# PreCharge.net
KiCad netlist of a schematic drawn in Altium Designer
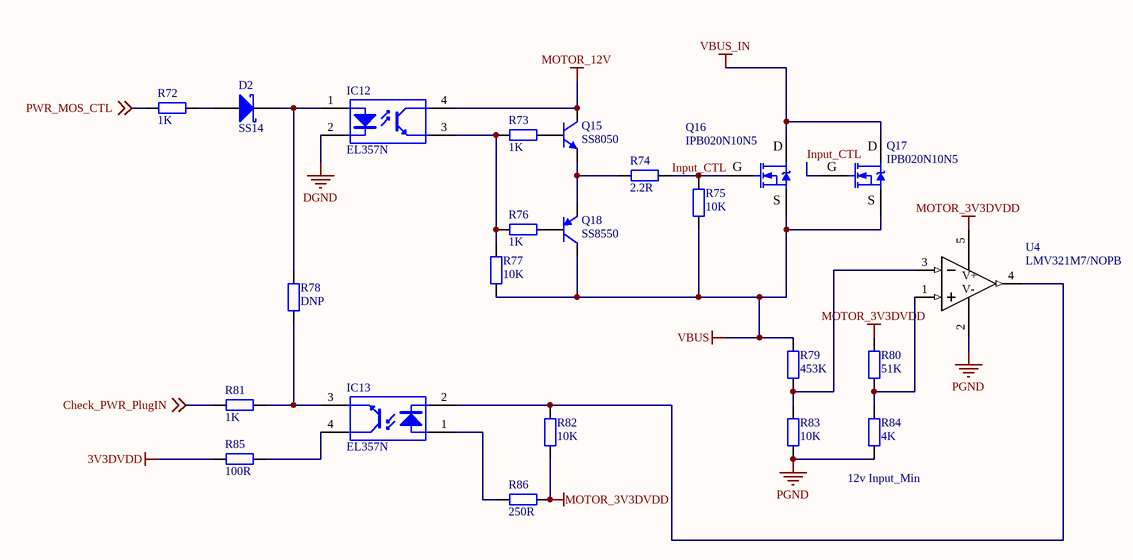
[diagram p0: PreCharge.SchDoc]

(export (version "E")
  (design (tool "Eeschema 10.0.6"))
  (components
    (comp (ref "D2")
      (value "SS14")
      (footprint "SMA")
      (description "肖特基二极管")
      (libsource (lib "0.2 -  二极管-整流桥") (part "SS14"))
    )
    (comp (ref "IC12")
      (value "EL357N")
      (footprint "DIP4-300")
      (description "线性光耦")
      (fields (field (name "版权归属") "封装库来自淘宝 ID：黄晶宝石"))
      (libsource (lib "1.2 - 传感元件") (part "EL357N"))
    )
    (comp (ref "IC13")
      (value "EL357N")
      (footprint "DIP4-300")
      (description "线性光耦")
      (fields (field (name "版权归属") "封装库来自淘宝 ID：黄晶宝石"))
      (libsource (lib "1.2 - 传感元件") (part "EL357N"))
    )
    (comp (ref "Q15")
      (value "SS8050")
      (footprint "SOT23-3N")
      (description "高频放大-NPN型")
      (fields (field (name "版权归属") "封装库来自淘宝 ID：黄晶宝石"))
      (libsource (lib "0.4 - 三极管") (part "8050-SMD"))
    )
    (comp (ref "Q16")
      (value "IPB020N10N5")
      (footprint "TO252")
      (description "N沟道场效应管")
      (libsource (lib "0.5 - 场效应管-可控硅") (part "SI2302"))
    )
    (comp (ref "Q17")
      (value "IPB020N10N5")
      (footprint "TO252")
      (description "N沟道场效应管")
      (libsource (lib "0.5 - 场效应管-可控硅") (part "SI2302"))
    )
    (comp (ref "Q18")
      (value "SS8550")
      (footprint "SOT23-3N")
      (description "高频放大-PNP型")
      (fields (field (name "版权归属") "封装库来自淘宝 ID：黄晶宝石"))
      (libsource (lib "0.4 - 三极管") (part "8550-SMD"))
    )
    (comp (ref "R72")
      (value "1K")
      (footprint "R 0603_L")
      (description "贴片电阻")
      (libsource (lib "0.1 - 电阻-电容-电感") (part "R"))
    )
    (comp (ref "R73")
      (value "1K")
      (footprint "R 0603_L")
      (description "贴片电阻")
      (libsource (lib "0.1 - 电阻-电容-电感") (part "R"))
    )
    (comp (ref "R74")
      (value "2.2R")
      (footprint "R 0603_L")
      (description "贴片电阻")
      (libsource (lib "0.1 - 电阻-电容-电感") (part "R"))
    )
    (comp (ref "R75")
      (value "10K")
      (footprint "R 0603_L")
      (description "贴片电阻")
      (libsource (lib "0.1 - 电阻-电容-电感") (part "R"))
    )
    (comp (ref "R76")
      (value "1K")
      (footprint "R 0603_L")
      (description "贴片电阻")
      (libsource (lib "0.1 - 电阻-电容-电感") (part "R"))
    )
    (comp (ref "R77")
      (value "10K")
      (footprint "R 0603_L")
      (description "贴片电阻")
      (libsource (lib "0.1 - 电阻-电容-电感") (part "R"))
    )
    (comp (ref "R78")
      (value "DNP")
      (footprint "R 0603_L")
      (description "贴片电阻")
      (libsource (lib "0.1 - 电阻-电容-电感") (part "R"))
    )
    (comp (ref "R79")
      (value "453K")
      (footprint "R 0603_L")
      (description "贴片电阻")
      (libsource (lib "0.1 - 电阻-电容-电感") (part "R"))
    )
    (comp (ref "R80")
      (value "51K")
      (footprint "R 0603_L")
      (description "贴片电阻")
      (libsource (lib "0.1 - 电阻-电容-电感") (part "R"))
    )
    (comp (ref "R81")
      (value "1K")
      (footprint "R 0603_L")
      (description "贴片电阻")
      (libsource (lib "0.1 - 电阻-电容-电感") (part "R"))
    )
    (comp (ref "R82")
      (value "10K")
      (footprint "R 0603_L")
      (description "贴片电阻")
      (libsource (lib "0.1 - 电阻-电容-电感") (part "R"))
    )
    (comp (ref "R83")
      (value "10K")
      (footprint "R 0603_L")
      (description "贴片电阻")
      (libsource (lib "0.1 - 电阻-电容-电感") (part "R"))
    )
    (comp (ref "R84")
      (value "4K")
      (footprint "R 0603_L")
      (description "贴片电阻")
      (libsource (lib "0.1 - 电阻-电容-电感") (part "R"))
    )
    (comp (ref "R85")
      (value "100R")
      (footprint "R 0603_L")
      (description "贴片电阻")
      (libsource (lib "0.1 - 电阻-电容-电感") (part "R"))
    )
    (comp (ref "R86")
      (value "250R")
      (footprint "R 0603_L")
      (description "贴片电阻")
      (libsource (lib "0.1 - 电阻-电容-电感") (part "R"))
    )
    (comp (ref "U4")
      (value "LMV321M7/NOPB")
      (footprint "MAA05A")
      (description "No Description Available")
      (fields
        (field (name "PARTNUMBER") "LMV321M7")
        (field (name "MANUFACTURER") "NationalSemiconductor")
        (field (name "COPYRIGHT") "Copyright (C) 2023 Ultra Librarian. All rights reserved.")
        (field (name "PUBLISHER") "NationalSemiconductor")
      )
      (libsource (lib "SkylakeADSchLib") (part "LMV321M7/NOPB"))
    )
  )
  (nets
    (net (code "1") (name "/Input_CTL") (class "Default")
      (node (ref "Q16") (pin "1") (pinfunction "G_1") (pintype "passive"))
      (node (ref "Q17") (pin "1") (pinfunction "G_1") (pintype "passive"))
      (node (ref "R74") (pin "1") (pinfunction "1_1") (pintype "passive"))
      (node (ref "R75") (pin "1") (pinfunction "1_1") (pintype "passive"))
    )
    (net (code "2") (name "3V3DVDD") (class "Default")
      (node (ref "R85") (pin "1") (pinfunction "1_1") (pintype "passive"))
    )
    (net (code "3") (name "Check_PWR_PlugIN") (class "Default")
      (node (ref "R81") (pin "2") (pinfunction "2_2") (pintype "passive"))
    )
    (net (code "4") (name "DGND") (class "Default")
      (node (ref "IC12") (pin "2") (pinfunction "K_2") (pintype "passive"))
    )
    (net (code "5") (name "MOTOR_3V3DVDD") (class "Default")
      (node (ref "R80") (pin "1") (pinfunction "1_1") (pintype "passive"))
      (node (ref "R82") (pin "2") (pinfunction "2_2") (pintype "passive"))
      (node (ref "R86") (pin "1") (pinfunction "1_1") (pintype "passive"))
      (node (ref "U4") (pin "5") (pinfunction "V+_5") (pintype "power_in"))
    )
    (net (code "6") (name "MOTOR_12V") (class "Default")
      (node (ref "IC12") (pin "4") (pinfunction "C_4") (pintype "passive"))
      (node (ref "Q15") (pin "3") (pinfunction "C_3") (pintype "passive"))
    )
    (net (code "7") (name "Net-(D2-A)") (class "Default")
      (node (ref "D2") (pin "1") (pinfunction "A_1") (pintype "passive"))
      (node (ref "R72") (pin "1") (pinfunction "1_1") (pintype "passive"))
    )
    (net (code "8") (name "Net-(D2-K)") (class "Default")
      (node (ref "D2") (pin "2") (pinfunction "K_2") (pintype "passive"))
      (node (ref "IC12") (pin "1") (pinfunction "A_1") (pintype "passive"))
      (node (ref "R78") (pin "1") (pinfunction "1_1") (pintype "passive"))
    )
    (net (code "9") (name "Net-(IC12-E)") (class "Default")
      (node (ref "IC12") (pin "3") (pinfunction "E_3") (pintype "passive"))
      (node (ref "R73") (pin "2") (pinfunction "2_2") (pintype "passive"))
      (node (ref "R76") (pin "2") (pinfunction "2_2") (pintype "passive"))
      (node (ref "R77") (pin "1") (pinfunction "1_1") (pintype "passive"))
    )
    (net (code "10") (name "Net-(IC13-A)") (class "Default")
      (node (ref "IC13") (pin "1") (pinfunction "A_1") (pintype "passive"))
      (node (ref "R86") (pin "2") (pinfunction "2_2") (pintype "passive"))
    )
    (net (code "11") (name "Net-(IC13-C)") (class "Default")
      (node (ref "IC13") (pin "4") (pinfunction "C_4") (pintype "passive"))
      (node (ref "R85") (pin "2") (pinfunction "2_2") (pintype "passive"))
    )
    (net (code "12") (name "Net-(IC13-E)") (class "Default")
      (node (ref "IC13") (pin "3") (pinfunction "E_3") (pintype "passive"))
      (node (ref "R78") (pin "2") (pinfunction "2_2") (pintype "passive"))
      (node (ref "R81") (pin "1") (pinfunction "1_1") (pintype "passive"))
    )
    (net (code "13") (name "Net-(IC13-K)") (class "Default")
      (node (ref "IC13") (pin "2") (pinfunction "K_2") (pintype "passive"))
      (node (ref "R82") (pin "1") (pinfunction "1_1") (pintype "passive"))
      (node (ref "U4") (pin "4") (pinfunction "OUT_4") (pintype "output"))
    )
    (net (code "14") (name "Net-(Q15-B)") (class "Default")
      (node (ref "Q15") (pin "1") (pinfunction "B_1") (pintype "passive"))
      (node (ref "R73") (pin "1") (pinfunction "1_1") (pintype "passive"))
    )
    (net (code "15") (name "Net-(Q15-E)") (class "Default")
      (node (ref "Q15") (pin "2") (pinfunction "E_2") (pintype "passive"))
      (node (ref "Q18") (pin "2") (pinfunction "E_2") (pintype "passive"))
      (node (ref "R74") (pin "2") (pinfunction "2_2") (pintype "passive"))
    )
    (net (code "16") (name "Net-(Q18-B)") (class "Default")
      (node (ref "Q18") (pin "1") (pinfunction "B_1") (pintype "passive"))
      (node (ref "R76") (pin "1") (pinfunction "1_1") (pintype "passive"))
    )
    (net (code "17") (name "Net-(U4-IN+)") (class "Default")
      (node (ref "R80") (pin "2") (pinfunction "2_2") (pintype "passive"))
      (node (ref "R84") (pin "1") (pinfunction "1_1") (pintype "passive"))
      (node (ref "U4") (pin "1") (pinfunction "IN+_1") (pintype "input"))
    )
    (net (code "18") (name "Net-(U4-IN-)") (class "Default")
      (node (ref "R79") (pin "2") (pinfunction "2_2") (pintype "passive"))
      (node (ref "R83") (pin "1") (pinfunction "1_1") (pintype "passive"))
      (node (ref "U4") (pin "3") (pinfunction "IN-_3") (pintype "input"))
    )
    (net (code "19") (name "PGND") (class "Default")
      (node (ref "R83") (pin "2") (pinfunction "2_2") (pintype "passive"))
      (node (ref "R84") (pin "2") (pinfunction "2_2") (pintype "passive"))
      (node (ref "U4") (pin "2") (pinfunction "V-_2") (pintype "power_in"))
    )
    (net (code "20") (name "PWR_MOS_CTL") (class "Default")
      (node (ref "R72") (pin "2") (pinfunction "2_2") (pintype "passive"))
    )
    (net (code "21") (name "VBUS") (class "Default")
      (node (ref "Q16") (pin "2") (pinfunction "S_2") (pintype "passive"))
      (node (ref "Q17") (pin "2") (pinfunction "S_2") (pintype "passive"))
      (node (ref "Q18") (pin "3") (pinfunction "C_3") (pintype "passive"))
      (node (ref "R75") (pin "2") (pinfunction "2_2") (pintype "passive"))
      (node (ref "R77") (pin "2") (pinfunction "2_2") (pintype "passive"))
      (node (ref "R79") (pin "1") (pinfunction "1_1") (pintype "passive"))
    )
    (net (code "22") (name "VBUS_IN") (class "Default")
      (node (ref "Q16") (pin "3") (pinfunction "D_3") (pintype "passive"))
      (node (ref "Q17") (pin "3") (pinfunction "D_3") (pintype "passive"))
    )
  )
)
